# power-dist-board.net
KiCad netlist of a schematic drawn in EAGLE
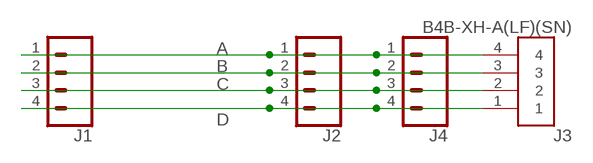
[diagram p0: schematic, sheet 1]

(export (version "E")
  (design (tool "Eeschema 10.0.6"))
  (components
    (comp (ref "J1")
      (value "CONN_04")
      (footprint "eagle-import:1X04")
      (libsource (lib "eagle-import") (part "CONN_04"))
    )
    (comp (ref "J2")
      (value "CONN_04")
      (footprint "eagle-import:1X04")
      (libsource (lib "eagle-import") (part "CONN_04"))
    )
    (comp (ref "J3")
      (value "B4B-XH-A(LF)(SN)")
      (footprint "eagle-import:JST_B4B-XH-A(LF)(SN)")
      (fields (field (name "DIGI-KEY_PART_NUMBER") "455-2249-ND") (field (name "MF") "JST Sales"))
      (libsource (lib "eagle-import") (part "B4B-XH-A(LF)(SN)"))
    )
    (comp (ref "J4")
      (value "CONN_04")
      (footprint "eagle-import:1X04")
      (libsource (lib "eagle-import") (part "CONN_04"))
    )
  )
  (nets
    (net (code "1") (name "/A") (class "Default")
      (node (ref "J1") (pin "1") (pinfunction "1_1") (pintype "passive"))
      (node (ref "J2") (pin "1") (pinfunction "1_1") (pintype "passive"))
      (node (ref "J3") (pin "4") (pinfunction "4_4") (pintype "passive"))
      (node (ref "J4") (pin "1") (pinfunction "1_1") (pintype "passive"))
    )
    (net (code "2") (name "/B") (class "Default")
      (node (ref "J1") (pin "2") (pinfunction "2_2") (pintype "passive"))
      (node (ref "J2") (pin "2") (pinfunction "2_2") (pintype "passive"))
      (node (ref "J3") (pin "3") (pinfunction "3_3") (pintype "passive"))
      (node (ref "J4") (pin "2") (pinfunction "2_2") (pintype "passive"))
    )
    (net (code "3") (name "/C") (class "Default")
      (node (ref "J1") (pin "3") (pinfunction "3_3") (pintype "passive"))
      (node (ref "J2") (pin "3") (pinfunction "3_3") (pintype "passive"))
      (node (ref "J3") (pin "2") (pinfunction "2_2") (pintype "passive"))
      (node (ref "J4") (pin "3") (pinfunction "3_3") (pintype "passive"))
    )
    (net (code "4") (name "/D") (class "Default")
      (node (ref "J1") (pin "4") (pinfunction "4_4") (pintype "passive"))
      (node (ref "J2") (pin "4") (pinfunction "4_4") (pintype "passive"))
      (node (ref "J3") (pin "1") (pinfunction "1_1") (pintype "passive"))
      (node (ref "J4") (pin "4") (pinfunction "4_4") (pintype "passive"))
    )
  )
)
